# Driver.net
KiCad netlist of a schematic drawn in Altium Designer
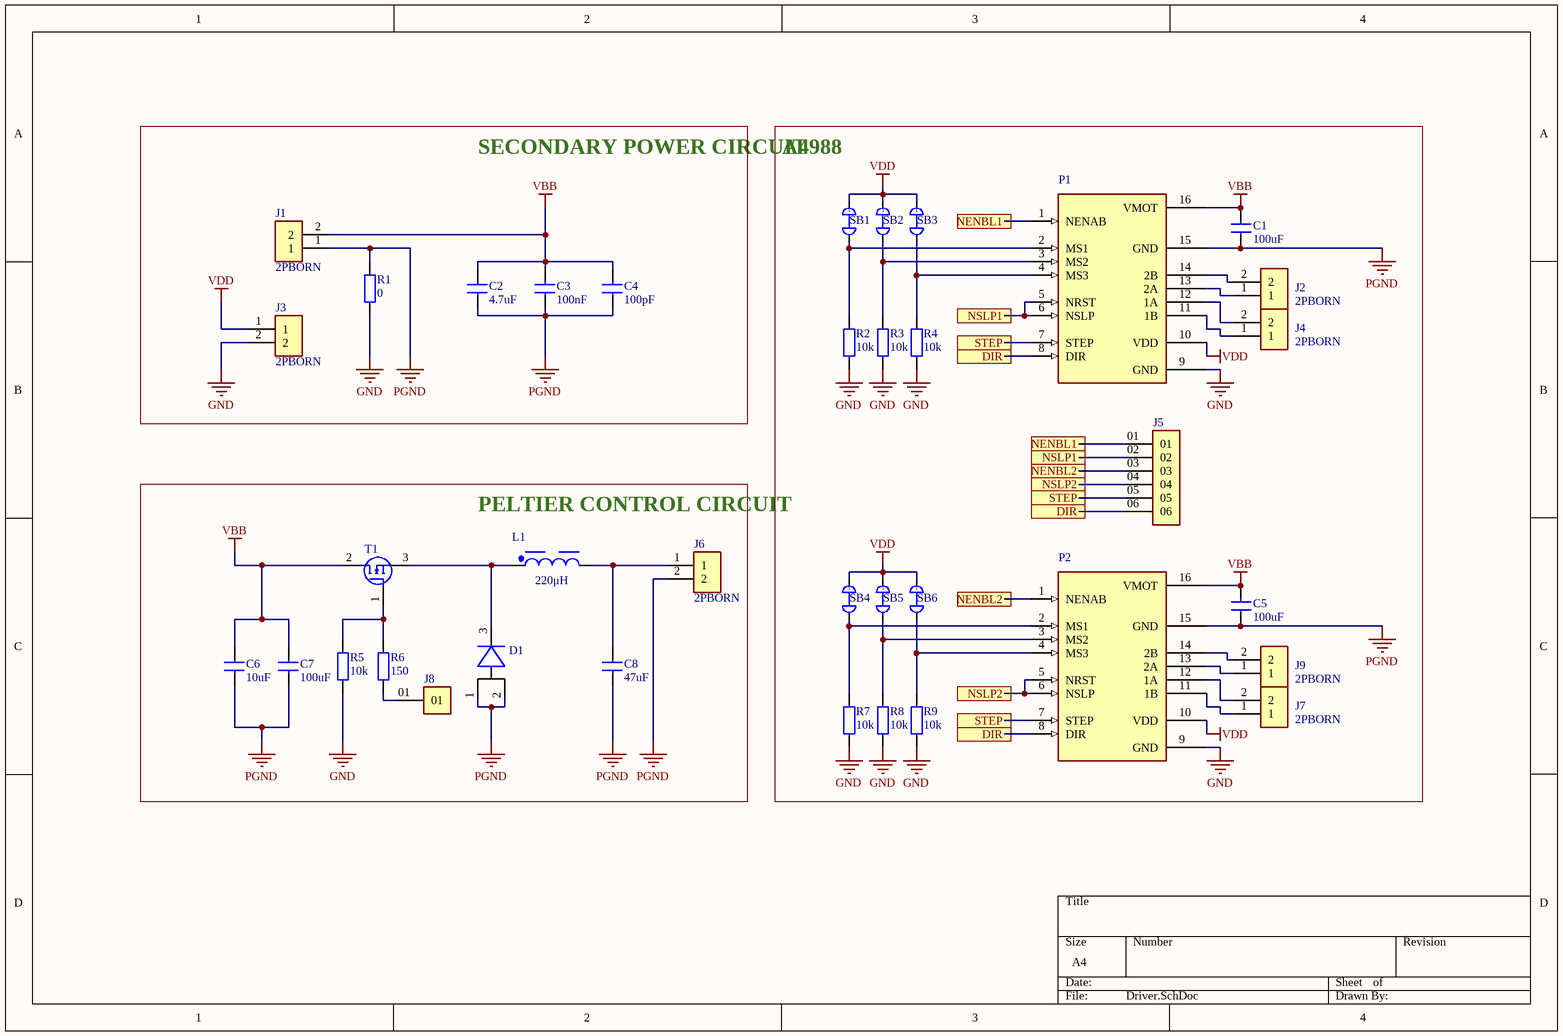
[diagram p0: Driver.SchDoc]

(export (version "E")
  (design (tool "Eeschema 10.0.6"))
  (components
    (comp (ref "C1")
      (value "100uF")
      (footprint "RES_0805")
      (description "Generic Capacitor")
      (libsource (lib "Components") (part "CAP_0805"))
    )
    (comp (ref "C2")
      (value "4.7uF")
      (footprint "RES_0805")
      (description "Generic Capacitor")
      (libsource (lib "Components") (part "CAP_0805"))
    )
    (comp (ref "C3")
      (value "100nF")
      (footprint "RES_0805")
      (description "Generic Capacitor")
      (libsource (lib "Components") (part "CAP_0805"))
    )
    (comp (ref "C4")
      (value "100pF")
      (footprint "RES_0805")
      (description "Generic Capacitor")
      (libsource (lib "Components") (part "CAP_0805"))
    )
    (comp (ref "C5")
      (value "100uF")
      (footprint "RES_0805")
      (description "Generic Capacitor")
      (libsource (lib "Components") (part "CAP_0805"))
    )
    (comp (ref "C6")
      (value "10uF")
      (footprint "RES_0805")
      (description "Generic Capacitor")
      (libsource (lib "") (part "CAP_0805_1"))
    )
    (comp (ref "C7")
      (value "100uF")
      (footprint "RES_0805")
      (description "Generic Capacitor")
      (libsource (lib "") (part "CAP_0805_1"))
    )
    (comp (ref "C8")
      (value "47uF")
      (footprint "RES_0805")
      (description "Generic Capacitor")
      (libsource (lib "") (part "CAP_0805_1"))
    )
    (comp (ref "D1")
      (value "DIODE_FSV15150V")
      (footprint "FSV15150V_TO-277")
      (libsource (lib "Components") (part "DIODE_FSV15150V"))
    )
    (comp (ref "J1")
      (value "2PBORN")
      (footprint "CUI_TB002-500-02BE")
      (description "2~24 Poles, Screw Type, Horizontal, 5.0 Pitch, 22~12 (AWG), Terminal Block Connector")
      (fields (field (name "MF") "Same Sky") (field (name "MP") "TB002-500-02BE"))
      (libsource (lib "") (part "2PBorn-TB002-500-02BE_2"))
    )
    (comp (ref "J2")
      (value "2PBORN")
      (footprint "CUI_TB002-500-02BE")
      (description "2~24 Poles, Screw Type, Horizontal, 5.0 Pitch, 22~12 (AWG), Terminal Block Connector")
      (fields (field (name "MF") "Same Sky") (field (name "MP") "TB002-500-02BE"))
      (libsource (lib "") (part "2PBorn-TB002-500-02BE_1"))
    )
    (comp (ref "J3")
      (value "2PBORN")
      (footprint "CUI_TB002-500-02BE")
      (description "2~24 Poles, Screw Type, Horizontal, 5.0 Pitch, 22~12 (AWG), Terminal Block Connector")
      (fields (field (name "MF") "Same Sky") (field (name "MP") "TB002-500-02BE"))
      (libsource (lib "Pines") (part "2PBorn-TB002-500-02BE"))
    )
    (comp (ref "J4")
      (value "2PBORN")
      (footprint "CUI_TB002-500-02BE")
      (description "2~24 Poles, Screw Type, Horizontal, 5.0 Pitch, 22~12 (AWG), Terminal Block Connector")
      (fields (field (name "MF") "Same Sky") (field (name "MP") "TB002-500-02BE"))
      (libsource (lib "") (part "2PBorn-TB002-500-02BE_1"))
    )
    (comp (ref "J5")
      (value "PIN_HEADER_6")
      (footprint "GEN_PIN6")
      (description "Generic 40 mils drill size, 100 mils step")
      (fields (field (name "MF") "Samtec Inc.") (field (name "MP") "TS-106-T-A"))
      (libsource (lib "Components") (part "PIN_HEADER_6"))
    )
    (comp (ref "J6")
      (value "2PBORN")
      (footprint "CUI_TB002-500-02BE")
      (description "2~24 Poles, Screw Type, Horizontal, 5.0 Pitch, 22~12 (AWG), Terminal Block Connector")
      (fields (field (name "MF") "Same Sky") (field (name "MP") "TB002-500-02BE"))
      (libsource (lib "Pines") (part "2PBorn-TB002-500-02BE"))
    )
    (comp (ref "J7")
      (value "2PBORN")
      (footprint "CUI_TB002-500-02BE")
      (description "2~24 Poles, Screw Type, Horizontal, 5.0 Pitch, 22~12 (AWG), Terminal Block Connector")
      (fields (field (name "MF") "Same Sky") (field (name "MP") "TB002-500-02BE"))
      (libsource (lib "") (part "2PBorn-TB002-500-02BE_1"))
    )
    (comp (ref "J8")
      (value "PIN_HEADER_1")
      (footprint "GEN_PIN1")
      (description "Generic 40 mils drill size, 100 mils step")
      (fields (field (name "MF") "Samtec") (field (name "MP") "TS-101-T-AA"))
      (libsource (lib "Components") (part "PIN_HEADER_1"))
    )
    (comp (ref "J9")
      (value "2PBORN")
      (footprint "CUI_TB002-500-02BE")
      (description "2~24 Poles, Screw Type, Horizontal, 5.0 Pitch, 22~12 (AWG), Terminal Block Connector")
      (fields (field (name "MF") "Same Sky") (field (name "MP") "TB002-500-02BE"))
      (libsource (lib "") (part "2PBorn-TB002-500-02BE_1"))
    )
    (comp (ref "L1")
      (value "220μH")
      (footprint "WE-HCF_2920")
      (description "WE-HCF SMT High Current Inductor, size 2920, 220μH, 8.15A, 40.1mΩ")
      (fields
        (field (name "MANUFACTURER PART NUMBER") "74437529203221")
        (field (name "MANUFACTURER") "Wurth Elektronik")
      )
      (libsource (lib "Components") (part "L220uH_74437529203221"))
    )
    (comp (ref "P1")
      (value "2x8_PINES")
      (footprint "PINES8x2-sep")
      (libsource (lib "Components") (part "2x8_PINES"))
    )
    (comp (ref "P2")
      (value "2x8_PINES")
      (footprint "PINES8x2-sep")
      (libsource (lib "Components") (part "2x8_PINES"))
    )
    (comp (ref "R1")
      (value "0")
      (footprint "RES_0805")
      (description "Generic Capacitor")
      (libsource (lib "Components") (part "RES_0805"))
    )
    (comp (ref "R2")
      (value "10k")
      (footprint "RES_0805")
      (description "Generic Capacitor")
      (libsource (lib "Components") (part "RES_0805"))
    )
    (comp (ref "R3")
      (value "10k")
      (footprint "RES_0805")
      (description "Generic Capacitor")
      (libsource (lib "Components") (part "RES_0805"))
    )
    (comp (ref "R4")
      (value "10k")
      (footprint "RES_0805")
      (description "Generic Capacitor")
      (libsource (lib "Components") (part "RES_0805"))
    )
    (comp (ref "R5")
      (value "10k")
      (footprint "RES_0805")
      (description "Generic Capacitor")
      (libsource (lib "Components") (part "RES_0805"))
    )
    (comp (ref "R6")
      (value "150")
      (footprint "RES_0805")
      (description "Generic Capacitor")
      (libsource (lib "Components") (part "RES_0805"))
    )
    (comp (ref "R7")
      (value "10k")
      (footprint "RES_0805")
      (description "Generic Capacitor")
      (libsource (lib "Components") (part "RES_0805"))
    )
    (comp (ref "R8")
      (value "10k")
      (footprint "RES_0805")
      (description "Generic Capacitor")
      (libsource (lib "Components") (part "RES_0805"))
    )
    (comp (ref "R9")
      (value "10k")
      (footprint "RES_0805")
      (description "Generic Capacitor")
      (libsource (lib "Components") (part "RES_0805"))
    )
    (comp (ref "SB1")
      (value "SolderBridge_Short")
      (footprint "SolderBridge_Short")
      (libsource (lib "Components") (part "SolderBridge_Short"))
    )
    (comp (ref "SB2")
      (value "SolderBridge_Short")
      (footprint "SolderBridge_Short")
      (libsource (lib "Components") (part "SolderBridge_Short"))
    )
    (comp (ref "SB3")
      (value "SolderBridge_Short")
      (footprint "SolderBridge_Short")
      (libsource (lib "Components") (part "SolderBridge_Short"))
    )
    (comp (ref "SB4")
      (value "SolderBridge_Short")
      (footprint "SolderBridge_Short")
      (libsource (lib "Components") (part "SolderBridge_Short"))
    )
    (comp (ref "SB5")
      (value "SolderBridge_Short")
      (footprint "SolderBridge_Short")
      (libsource (lib "Components") (part "SolderBridge_Short"))
    )
    (comp (ref "SB6")
      (value "SolderBridge_Short")
      (footprint "SolderBridge_Short")
      (libsource (lib "Components") (part "SolderBridge_Short"))
    )
    (comp (ref "T1")
      (value "NMOS-DMT10H010LK3")
      (footprint "MOSFET_TRANS_2DB1184Q-13")
      (libsource (lib "Components") (part "NMOS-DMT10H010LK3"))
    )
  )
  (nets
    (net (code "1") (name "/DIR") (class "Default")
      (node (ref "J5") (pin "06") (pinfunction "06_06") (pintype "passive"))
      (node (ref "P1") (pin "8") (pinfunction "DIR_8") (pintype "input"))
      (node (ref "P2") (pin "8") (pinfunction "DIR_8") (pintype "input"))
    )
    (net (code "2") (name "/NENBL1") (class "Default")
      (node (ref "J5") (pin "01") (pinfunction "01_01") (pintype "passive"))
      (node (ref "P1") (pin "1") (pinfunction "NENAB_1") (pintype "input"))
    )
    (net (code "3") (name "/NENBL2") (class "Default")
      (node (ref "J5") (pin "03") (pinfunction "03_03") (pintype "passive"))
      (node (ref "P2") (pin "1") (pinfunction "NENAB_1") (pintype "input"))
    )
    (net (code "4") (name "/NSLP1") (class "Default")
      (node (ref "J5") (pin "02") (pinfunction "02_02") (pintype "passive"))
      (node (ref "P1") (pin "5") (pinfunction "NRST_5") (pintype "input"))
      (node (ref "P1") (pin "6") (pinfunction "NSLP_6") (pintype "input"))
    )
    (net (code "5") (name "/NSLP2") (class "Default")
      (node (ref "J5") (pin "04") (pinfunction "04_04") (pintype "passive"))
      (node (ref "P2") (pin "5") (pinfunction "NRST_5") (pintype "input"))
      (node (ref "P2") (pin "6") (pinfunction "NSLP_6") (pintype "input"))
    )
    (net (code "6") (name "/STEP") (class "Default")
      (node (ref "J5") (pin "05") (pinfunction "05_05") (pintype "passive"))
      (node (ref "P1") (pin "7") (pinfunction "STEP_7") (pintype "input"))
      (node (ref "P2") (pin "7") (pinfunction "STEP_7") (pintype "input"))
    )
    (net (code "7") (name "GND") (class "Default")
      (node (ref "J3") (pin "2") (pinfunction "2_2") (pintype "passive"))
      (node (ref "P1") (pin "9") (pinfunction "GND_9") (pintype "passive"))
      (node (ref "P2") (pin "9") (pinfunction "GND_9") (pintype "passive"))
      (node (ref "R1") (pin "1") (pinfunction "1_1") (pintype "passive"))
      (node (ref "R2") (pin "1") (pinfunction "1_1") (pintype "passive"))
      (node (ref "R3") (pin "1") (pinfunction "1_1") (pintype "passive"))
      (node (ref "R4") (pin "1") (pinfunction "1_1") (pintype "passive"))
      (node (ref "R5") (pin "1") (pinfunction "1_1") (pintype "passive"))
      (node (ref "R7") (pin "1") (pinfunction "1_1") (pintype "passive"))
      (node (ref "R8") (pin "1") (pinfunction "1_1") (pintype "passive"))
      (node (ref "R9") (pin "1") (pinfunction "1_1") (pintype "passive"))
    )
    (net (code "8") (name "Net-(C8-Pad2)") (class "Default")
      (node (ref "C8") (pin "2") (pinfunction "2_2") (pintype "passive"))
      (node (ref "J6") (pin "1") (pinfunction "1_1") (pintype "passive"))
      (node (ref "L1") (pin "2") (pinfunction "2_2") (pintype "passive"))
    )
    (net (code "9") (name "Net-(D1-C)") (class "Default")
      (node (ref "D1") (pin "3") (pinfunction "C_3") (pintype "passive"))
      (node (ref "L1") (pin "1") (pinfunction "1_1") (pintype "passive"))
      (node (ref "T1") (pin "3") (pinfunction "S_3") (pintype "passive"))
    )
    (net (code "10") (name "Net-(J8-Pad01)") (class "Default")
      (node (ref "J8") (pin "01") (pinfunction "01_01") (pintype "passive"))
      (node (ref "R6") (pin "1") (pinfunction "1_1") (pintype "passive"))
    )
    (net (code "11") (name "Net-(P1-1A)") (class "Default")
      (node (ref "J4") (pin "2") (pinfunction "2_2") (pintype "passive"))
      (node (ref "P1") (pin "12") (pinfunction "1A_12") (pintype "passive"))
    )
    (net (code "12") (name "Net-(P1-1B)") (class "Default")
      (node (ref "J4") (pin "1") (pinfunction "1_1") (pintype "passive"))
      (node (ref "P1") (pin "11") (pinfunction "1B_11") (pintype "passive"))
    )
    (net (code "13") (name "Net-(P1-2A)") (class "Default")
      (node (ref "J2") (pin "1") (pinfunction "1_1") (pintype "passive"))
      (node (ref "P1") (pin "13") (pinfunction "2A_13") (pintype "passive"))
    )
    (net (code "14") (name "Net-(P1-2B)") (class "Default")
      (node (ref "J2") (pin "2") (pinfunction "2_2") (pintype "passive"))
      (node (ref "P1") (pin "14") (pinfunction "2B_14") (pintype "passive"))
    )
    (net (code "15") (name "Net-(P1-MS1)") (class "Default")
      (node (ref "P1") (pin "2") (pinfunction "MS1_2") (pintype "input"))
      (node (ref "R2") (pin "2") (pinfunction "2_2") (pintype "passive"))
      (node (ref "SB1") (pin "2") (pinfunction "2_2") (pintype "passive"))
    )
    (net (code "16") (name "Net-(P1-MS2)") (class "Default")
      (node (ref "P1") (pin "3") (pinfunction "MS2_3") (pintype "input"))
      (node (ref "R3") (pin "2") (pinfunction "2_2") (pintype "passive"))
      (node (ref "SB2") (pin "2") (pinfunction "2_2") (pintype "passive"))
    )
    (net (code "17") (name "Net-(P1-MS3)") (class "Default")
      (node (ref "P1") (pin "4") (pinfunction "MS3_4") (pintype "input"))
      (node (ref "R4") (pin "2") (pinfunction "2_2") (pintype "passive"))
      (node (ref "SB3") (pin "2") (pinfunction "2_2") (pintype "passive"))
    )
    (net (code "18") (name "Net-(P2-1A)") (class "Default")
      (node (ref "J7") (pin "2") (pinfunction "2_2") (pintype "passive"))
      (node (ref "P2") (pin "12") (pinfunction "1A_12") (pintype "passive"))
    )
    (net (code "19") (name "Net-(P2-1B)") (class "Default")
      (node (ref "J7") (pin "1") (pinfunction "1_1") (pintype "passive"))
      (node (ref "P2") (pin "11") (pinfunction "1B_11") (pintype "passive"))
    )
    (net (code "20") (name "Net-(P2-2A)") (class "Default")
      (node (ref "J9") (pin "1") (pinfunction "1_1") (pintype "passive"))
      (node (ref "P2") (pin "13") (pinfunction "2A_13") (pintype "passive"))
    )
    (net (code "21") (name "Net-(P2-2B)") (class "Default")
      (node (ref "J9") (pin "2") (pinfunction "2_2") (pintype "passive"))
      (node (ref "P2") (pin "14") (pinfunction "2B_14") (pintype "passive"))
    )
    (net (code "22") (name "Net-(P2-MS1)") (class "Default")
      (node (ref "P2") (pin "2") (pinfunction "MS1_2") (pintype "input"))
      (node (ref "R7") (pin "2") (pinfunction "2_2") (pintype "passive"))
      (node (ref "SB4") (pin "2") (pinfunction "2_2") (pintype "passive"))
    )
    (net (code "23") (name "Net-(P2-MS2)") (class "Default")
      (node (ref "P2") (pin "3") (pinfunction "MS2_3") (pintype "input"))
      (node (ref "R8") (pin "2") (pinfunction "2_2") (pintype "passive"))
      (node (ref "SB5") (pin "2") (pinfunction "2_2") (pintype "passive"))
    )
    (net (code "24") (name "Net-(P2-MS3)") (class "Default")
      (node (ref "P2") (pin "4") (pinfunction "MS3_4") (pintype "input"))
      (node (ref "R9") (pin "2") (pinfunction "2_2") (pintype "passive"))
      (node (ref "SB6") (pin "2") (pinfunction "2_2") (pintype "passive"))
    )
    (net (code "25") (name "Net-(T1-G)") (class "Default")
      (node (ref "R5") (pin "2") (pinfunction "2_2") (pintype "passive"))
      (node (ref "R6") (pin "2") (pinfunction "2_2") (pintype "passive"))
      (node (ref "T1") (pin "1") (pinfunction "G_1") (pintype "passive"))
    )
    (net (code "26") (name "PGND") (class "Default")
      (node (ref "C1") (pin "2") (pinfunction "2_2") (pintype "passive"))
      (node (ref "C2") (pin "1") (pinfunction "1_1") (pintype "passive"))
      (node (ref "C3") (pin "1") (pinfunction "1_1") (pintype "passive"))
      (node (ref "C4") (pin "1") (pinfunction "1_1") (pintype "passive"))
      (node (ref "C5") (pin "2") (pinfunction "2_2") (pintype "passive"))
      (node (ref "C6") (pin "1") (pinfunction "1_1") (pintype "passive"))
      (node (ref "C7") (pin "1") (pinfunction "1_1") (pintype "passive"))
      (node (ref "C8") (pin "1") (pinfunction "1_1") (pintype "passive"))
      (node (ref "D1") (pin "1") (pinfunction "A_1") (pintype "passive"))
      (node (ref "D1") (pin "2") (pinfunction "2_2") (pintype "passive"))
      (node (ref "J1") (pin "1") (pinfunction "1_1") (pintype "passive"))
      (node (ref "J6") (pin "2") (pinfunction "2_2") (pintype "passive"))
      (node (ref "P1") (pin "15") (pinfunction "GND_15") (pintype "passive"))
      (node (ref "P2") (pin "15") (pinfunction "GND_15") (pintype "passive"))
      (node (ref "R1") (pin "2") (pinfunction "2_2") (pintype "passive"))
    )
    (net (code "27") (name "VBB") (class "Default")
      (node (ref "C1") (pin "1") (pinfunction "1_1") (pintype "passive"))
      (node (ref "C2") (pin "2") (pinfunction "2_2") (pintype "passive"))
      (node (ref "C3") (pin "2") (pinfunction "2_2") (pintype "passive"))
      (node (ref "C4") (pin "2") (pinfunction "2_2") (pintype "passive"))
      (node (ref "C5") (pin "1") (pinfunction "1_1") (pintype "passive"))
      (node (ref "C6") (pin "2") (pinfunction "2_2") (pintype "passive"))
      (node (ref "C7") (pin "2") (pinfunction "2_2") (pintype "passive"))
      (node (ref "J1") (pin "2") (pinfunction "2_2") (pintype "passive"))
      (node (ref "P1") (pin "16") (pinfunction "VMOT_16") (pintype "passive"))
      (node (ref "P2") (pin "16") (pinfunction "VMOT_16") (pintype "passive"))
      (node (ref "T1") (pin "2") (pinfunction "D_2") (pintype "passive"))
    )
    (net (code "28") (name "VDD") (class "Default")
      (node (ref "J3") (pin "1") (pinfunction "1_1") (pintype "passive"))
      (node (ref "P1") (pin "10") (pinfunction "VDD_10") (pintype "passive"))
      (node (ref "P2") (pin "10") (pinfunction "VDD_10") (pintype "passive"))
      (node (ref "SB1") (pin "1") (pinfunction "1_1") (pintype "passive"))
      (node (ref "SB2") (pin "1") (pinfunction "1_1") (pintype "passive"))
      (node (ref "SB3") (pin "1") (pinfunction "1_1") (pintype "passive"))
      (node (ref "SB4") (pin "1") (pinfunction "1_1") (pintype "passive"))
      (node (ref "SB5") (pin "1") (pinfunction "1_1") (pintype "passive"))
      (node (ref "SB6") (pin "1") (pinfunction "1_1") (pintype "passive"))
    )
  )
)
